# XM-15_Typical_Application_Circuit.net
KiCad netlist of a schematic drawn in Altium Designer
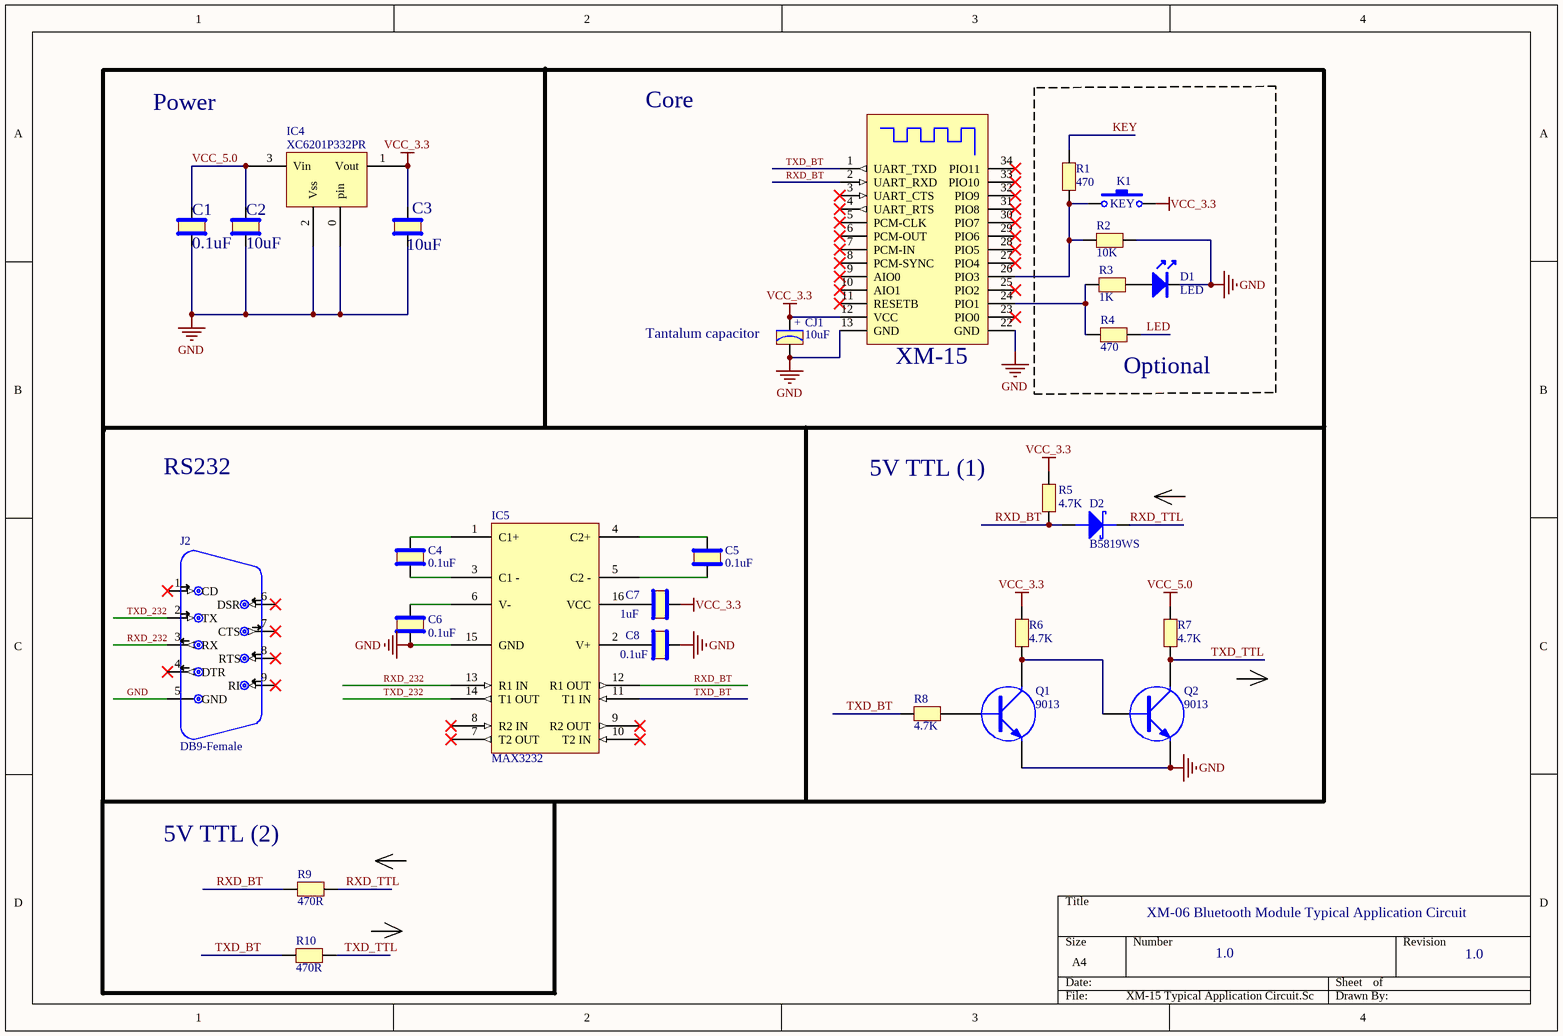
[diagram p0: XM-15 Typical Application Circuit.SchDoc]

(export (version "E")
  (design (tool "Eeschema 10.0.6"))
  (components
    (comp (ref "*1") (value "XM-15") (libsource (lib "wbh") (part "XM-101")))
    (comp (ref "C1") (value "0.1uF") (footprint "0603.RC") (libsource (lib "*") (part "CAP")))
    (comp (ref "C2") (value "10uF") (footprint "0603.RC") (libsource (lib "*") (part "CAP")))
    (comp (ref "C3") (value "10uF") (footprint "0603.RC") (libsource (lib "*") (part "CAP")))
    (comp (ref "C4") (value "0.1uF") (footprint "0603.RC") (libsource (lib "*") (part "CAP")))
    (comp (ref "C5") (value "0.1uF") (footprint "0603.RC") (libsource (lib "") (part "CAP_2")))
    (comp (ref "C6") (value "0.1uF") (footprint "0603.RC") (libsource (lib "*") (part "CAP")))
    (comp (ref "C7") (value "1uF") (footprint "0603.RC") (libsource (lib "") (part "CAP_1")))
    (comp (ref "C8") (value "0.1uF") (footprint "0603.RC") (libsource (lib "") (part "CAP_1")))
    (comp (ref "CJ1") (value "10uF") (footprint "1206.DC") (libsource (lib "wbh") (part "CAPJS")))
    (comp (ref "D1") (value "LED") (footprint "0603+") (libsource (lib "*") (part "LED")))
    (comp (ref "D2")
      (value "B5819WS")
      (footprint "SOD-323 - SMT")
      (description "Schottky Diode")
      (libsource (lib "wbh") (part "DIODE SCHOTTKY"))
    )
    (comp (ref "IC4") (value "XC6201P332PR") (footprint "SOT-89") (libsource (lib "*") (part "XC6201P301PR")))
    (comp (ref "IC5") (value "MAX3232") (footprint "SOP-16(N)") (libsource (lib "wbh") (part "MAX3232")))
    (comp (ref "J2") (value "DB9-Female") (footprint "DB9-F - 90") (libsource (lib "wbh") (part "DB9-F")))
    (comp (ref "K1") (value "KEY") (footprint "KEY-SS204") (libsource (lib "wbh") (part "SW-KEYSMT1")))
    (comp (ref "Q1")
      (value "9013")
      (footprint "SMT-SOT23MOS")
      (description "NPN Transistor")
      (libsource (lib "wbh") (part "NPN"))
    )
    (comp (ref "Q2")
      (value "9013")
      (footprint "SMT-SOT23MOS")
      (description "NPN Transistor")
      (libsource (lib "wbh") (part "NPN"))
    )
    (comp (ref "R1") (value "470") (footprint "0603.RC") (libsource (lib "") (part "RES_1")))
    (comp (ref "R2") (value "10K") (footprint "0603.RC") (libsource (lib "wbh") (part "RES")))
    (comp (ref "R3") (value "1K") (footprint "0603.RC") (libsource (lib "wbh") (part "RES")))
    (comp (ref "R4") (value "470") (footprint "0603.RC") (libsource (lib "wbh") (part "RES")))
    (comp (ref "R5") (value "4.7K") (footprint "0603.RC") (libsource (lib "") (part "RES_2")))
    (comp (ref "R6") (value "4.7K") (footprint "0603.RC") (libsource (lib "") (part "RES_3")))
    (comp (ref "R7") (value "4.7K") (footprint "0603.RC") (libsource (lib "") (part "RES_3")))
    (comp (ref "R8") (value "4.7K") (footprint "0603.RC") (libsource (lib "") (part "RES_1")))
    (comp (ref "R9") (value "470R") (footprint "0603.RC") (libsource (lib "") (part "RES_1")))
    (comp (ref "R10") (value "470R") (footprint "0603.RC") (libsource (lib "") (part "RES_1")))
  )
  (nets
    (net (code "1") (name "/KEY") (class "Default")
      (node (ref "R1") (pin "1") (pinfunction "1_1") (pintype "passive"))
    )
    (net (code "2") (name "/LED") (class "Default")
      (node (ref "R4") (pin "1") (pinfunction "1_1") (pintype "passive"))
    )
    (net (code "3") (name "/RXD_232") (class "Default")
      (node (ref "IC5") (pin "13") (pinfunction "R1_IN_13") (pintype "input"))
      (node (ref "J2") (pin "3") (pinfunction "RX_3") (pintype "output"))
    )
    (net (code "4") (name "/RXD_BT") (class "Default")
      (node (ref "*1") (pin "2") (pinfunction "UART_RXD_2") (pintype "input"))
      (node (ref "D2") (pin "1") (pinfunction "1_1") (pintype "passive"))
      (node (ref "IC5") (pin "12") (pinfunction "R1_OUT_12") (pintype "output"))
      (node (ref "R5") (pin "1") (pinfunction "1_1") (pintype "passive"))
      (node (ref "R9") (pin "2") (pinfunction "2_2") (pintype "passive"))
    )
    (net (code "5") (name "/RXD_TTL") (class "Default")
      (node (ref "D2") (pin "2") (pinfunction "2_2") (pintype "passive"))
      (node (ref "R9") (pin "1") (pinfunction "1_1") (pintype "passive"))
    )
    (net (code "6") (name "/TXD_232") (class "Default")
      (node (ref "IC5") (pin "14") (pinfunction "T1_OUT_14") (pintype "output"))
      (node (ref "J2") (pin "2") (pinfunction "TX_2") (pintype "input"))
    )
    (net (code "7") (name "/TXD_BT") (class "Default")
      (node (ref "*1") (pin "1") (pinfunction "UART_TXD_1") (pintype "output"))
      (node (ref "IC5") (pin "11") (pinfunction "T1_IN_11") (pintype "input"))
      (node (ref "R10") (pin "2") (pinfunction "2_2") (pintype "passive"))
      (node (ref "R8") (pin "2") (pinfunction "2_2") (pintype "passive"))
    )
    (net (code "8") (name "/TXD_TTL") (class "Default")
      (node (ref "Q2") (pin "D") (pinfunction "D_D") (pintype "passive"))
      (node (ref "R10") (pin "1") (pinfunction "1_1") (pintype "passive"))
      (node (ref "R7") (pin "1") (pinfunction "1_1") (pintype "passive"))
    )
    (net (code "9") (name "GND") (class "Default")
      (node (ref "*1") (pin "13") (pinfunction "GND_13") (pintype "passive"))
      (node (ref "*1") (pin "22") (pinfunction "GND_22") (pintype "passive"))
      (node (ref "C1") (pin "1") (pinfunction "1_1") (pintype "passive"))
      (node (ref "C2") (pin "1") (pinfunction "1_1") (pintype "passive"))
      (node (ref "C3") (pin "1") (pinfunction "1_1") (pintype "passive"))
      (node (ref "C6") (pin "1") (pinfunction "1_1") (pintype "passive"))
      (node (ref "C8") (pin "1") (pinfunction "1_1") (pintype "passive"))
      (node (ref "CJ1") (pin "K") (pinfunction "K_K") (pintype "passive"))
      (node (ref "D1") (pin "K") (pintype "passive"))
      (node (ref "IC4") (pin "0") (pinfunction "pin_0") (pintype "passive"))
      (node (ref "IC4") (pin "2") (pinfunction "Vss_2") (pintype "passive"))
      (node (ref "IC5") (pin "15") (pinfunction "GND_15") (pintype "power_in"))
      (node (ref "J2") (pin "5") (pinfunction "GND_5") (pintype "power_in"))
      (node (ref "Q1") (pin "S") (pinfunction "S_S") (pintype "passive"))
      (node (ref "Q2") (pin "S") (pinfunction "S_S") (pintype "passive"))
      (node (ref "R2") (pin "1") (pinfunction "1_1") (pintype "passive"))
    )
    (net (code "10") (name "Net-(*1-PIO1)") (class "Default")
      (node (ref "*1") (pin "24") (pinfunction "PIO1_24") (pintype "passive"))
      (node (ref "R3") (pin "2") (pinfunction "2_2") (pintype "passive"))
      (node (ref "R4") (pin "2") (pinfunction "2_2") (pintype "passive"))
    )
    (net (code "11") (name "Net-(*1-PIO3)") (class "Default")
      (node (ref "*1") (pin "26") (pinfunction "PIO3_26") (pintype "passive"))
      (node (ref "K1") (pin "2") (pinfunction "2_2") (pintype "passive"))
      (node (ref "R1") (pin "2") (pinfunction "2_2") (pintype "passive"))
      (node (ref "R2") (pin "2") (pinfunction "2_2") (pintype "passive"))
    )
    (net (code "12") (name "Net-(D1-PadA)") (class "Default")
      (node (ref "D1") (pin "A") (pintype "passive"))
      (node (ref "R3") (pin "1") (pinfunction "1_1") (pintype "passive"))
    )
    (net (code "13") (name "Net-(IC5-C1+)") (class "Default")
      (node (ref "C4") (pin "2") (pinfunction "2_2") (pintype "passive"))
      (node (ref "IC5") (pin "1") (pinfunction "C1+_1") (pintype "passive"))
    )
    (net (code "14") (name "Net-(IC5-C1_-)") (class "Default")
      (node (ref "C4") (pin "1") (pinfunction "1_1") (pintype "passive"))
      (node (ref "IC5") (pin "3") (pinfunction "C1_-_3") (pintype "passive"))
    )
    (net (code "15") (name "Net-(IC5-C2+)") (class "Default")
      (node (ref "C5") (pin "1") (pinfunction "1_1") (pintype "passive"))
      (node (ref "IC5") (pin "4") (pinfunction "C2+_4") (pintype "passive"))
    )
    (net (code "16") (name "Net-(IC5-C2_-)") (class "Default")
      (node (ref "C5") (pin "2") (pinfunction "2_2") (pintype "passive"))
      (node (ref "IC5") (pin "5") (pinfunction "C2_-_5") (pintype "passive"))
    )
    (net (code "17") (name "Net-(IC5-V+)") (class "Default")
      (node (ref "C8") (pin "2") (pinfunction "2_2") (pintype "passive"))
      (node (ref "IC5") (pin "2") (pinfunction "V+_2") (pintype "passive"))
    )
    (net (code "18") (name "Net-(IC5-V-)") (class "Default")
      (node (ref "C6") (pin "2") (pinfunction "2_2") (pintype "passive"))
      (node (ref "IC5") (pin "6") (pinfunction "V-_6") (pintype "power_in"))
    )
    (net (code "19") (name "Net-(IC5-VCC)") (class "Default")
      (node (ref "C7") (pin "2") (pinfunction "2_2") (pintype "passive"))
      (node (ref "IC5") (pin "16") (pinfunction "VCC_16") (pintype "power_in"))
    )
    (net (code "20") (name "Net-(Q1-PadD)") (class "Default")
      (node (ref "Q1") (pin "D") (pinfunction "D_D") (pintype "passive"))
      (node (ref "Q2") (pin "G") (pinfunction "G_G") (pintype "passive"))
      (node (ref "R6") (pin "1") (pinfunction "1_1") (pintype "passive"))
    )
    (net (code "21") (name "Net-(Q1-PadG)") (class "Default")
      (node (ref "Q1") (pin "G") (pinfunction "G_G") (pintype "passive"))
      (node (ref "R8") (pin "1") (pinfunction "1_1") (pintype "passive"))
    )
    (net (code "22") (name "VCC_3.3") (class "Default")
      (node (ref "*1") (pin "12") (pinfunction "VCC_12") (pintype "power_in"))
      (node (ref "C3") (pin "2") (pinfunction "2_2") (pintype "passive"))
      (node (ref "C7") (pin "1") (pinfunction "1_1") (pintype "passive"))
      (node (ref "CJ1") (pin "A") (pinfunction "A_A") (pintype "passive"))
      (node (ref "IC4") (pin "1") (pinfunction "Vout_1") (pintype "passive"))
      (node (ref "K1") (pin "1") (pinfunction "1_1") (pintype "passive"))
      (node (ref "R5") (pin "2") (pinfunction "2_2") (pintype "passive"))
      (node (ref "R6") (pin "2") (pinfunction "2_2") (pintype "passive"))
    )
    (net (code "23") (name "VCC_5.0") (class "Default")
      (node (ref "C1") (pin "2") (pinfunction "2_2") (pintype "passive"))
      (node (ref "C2") (pin "2") (pinfunction "2_2") (pintype "passive"))
      (node (ref "IC4") (pin "3") (pinfunction "Vin_3") (pintype "passive"))
      (node (ref "R7") (pin "2") (pinfunction "2_2") (pintype "passive"))
    )
    (net (code "24") (name "unconnected-(*1-AIO0-Pad9)") (class "Default")
      (node (ref "*1") (pin "9") (pinfunction "AIO0_9") (pintype "passive+no_connect"))
    )
    (net (code "25") (name "unconnected-(*1-AIO1-Pad10)") (class "Default")
      (node (ref "*1") (pin "10") (pinfunction "AIO1_10") (pintype "passive+no_connect"))
    )
    (net (code "26") (name "unconnected-(*1-PCM-CLK-Pad5)") (class "Default")
      (node (ref "*1") (pin "5") (pinfunction "PCM-CLK_5") (pintype "passive+no_connect"))
    )
    (net (code "27") (name "unconnected-(*1-PCM-IN-Pad7)") (class "Default")
      (node (ref "*1") (pin "7") (pinfunction "PCM-IN_7") (pintype "passive+no_connect"))
    )
    (net (code "28") (name "unconnected-(*1-PCM-OUT-Pad6)") (class "Default")
      (node (ref "*1") (pin "6") (pinfunction "PCM-OUT_6") (pintype "passive+no_connect"))
    )
    (net (code "29") (name "unconnected-(*1-PCM-SYNC-Pad8)") (class "Default")
      (node (ref "*1") (pin "8") (pinfunction "PCM-SYNC_8") (pintype "passive+no_connect"))
    )
    (net (code "30") (name "unconnected-(*1-PIO0-Pad23)") (class "Default")
      (node (ref "*1") (pin "23") (pinfunction "PIO0_23") (pintype "passive+no_connect"))
    )
    (net (code "31") (name "unconnected-(*1-PIO2-Pad25)") (class "Default")
      (node (ref "*1") (pin "25") (pinfunction "PIO2_25") (pintype "passive+no_connect"))
    )
    (net (code "32") (name "unconnected-(*1-PIO4-Pad27)") (class "Default")
      (node (ref "*1") (pin "27") (pinfunction "PIO4_27") (pintype "passive+no_connect"))
    )
    (net (code "33") (name "unconnected-(*1-PIO5-Pad28)") (class "Default")
      (node (ref "*1") (pin "28") (pinfunction "PIO5_28") (pintype "passive+no_connect"))
    )
    (net (code "34") (name "unconnected-(*1-PIO6-Pad29)") (class "Default")
      (node (ref "*1") (pin "29") (pinfunction "PIO6_29") (pintype "passive+no_connect"))
    )
    (net (code "35") (name "unconnected-(*1-PIO7-Pad30)") (class "Default")
      (node (ref "*1") (pin "30") (pinfunction "PIO7_30") (pintype "passive+no_connect"))
    )
    (net (code "36") (name "unconnected-(*1-PIO8-Pad31)") (class "Default")
      (node (ref "*1") (pin "31") (pinfunction "PIO8_31") (pintype "passive+no_connect"))
    )
    (net (code "37") (name "unconnected-(*1-PIO9-Pad32)") (class "Default")
      (node (ref "*1") (pin "32") (pinfunction "PIO9_32") (pintype "passive+no_connect"))
    )
    (net (code "38") (name "unconnected-(*1-PIO10-Pad33)") (class "Default")
      (node (ref "*1") (pin "33") (pinfunction "PIO10_33") (pintype "passive+no_connect"))
    )
    (net (code "39") (name "unconnected-(*1-PIO11-Pad34)") (class "Default")
      (node (ref "*1") (pin "34") (pinfunction "PIO11_34") (pintype "passive+no_connect"))
    )
    (net (code "40") (name "unconnected-(*1-RESETB-Pad11)") (class "Default")
      (node (ref "*1") (pin "11") (pinfunction "RESETB_11") (pintype "passive+no_connect"))
    )
    (net (code "41") (name "unconnected-(*1-UART_CTS-Pad3)") (class "Default")
      (node (ref "*1") (pin "3") (pinfunction "UART_CTS_3") (pintype "input+no_connect"))
    )
    (net (code "42") (name "unconnected-(*1-UART_RTS-Pad4)") (class "Default")
      (node (ref "*1") (pin "4") (pinfunction "UART_RTS_4") (pintype "output+no_connect"))
    )
    (net (code "43") (name "unconnected-(IC5-R2_IN-Pad8)") (class "Default")
      (node (ref "IC5") (pin "8") (pinfunction "R2_IN_8") (pintype "input+no_connect"))
    )
    (net (code "44") (name "unconnected-(IC5-R2_OUT-Pad9)") (class "Default")
      (node (ref "IC5") (pin "9") (pinfunction "R2_OUT_9") (pintype "output+no_connect"))
    )
    (net (code "45") (name "unconnected-(IC5-T2_IN-Pad10)") (class "Default")
      (node (ref "IC5") (pin "10") (pinfunction "T2_IN_10") (pintype "input+no_connect"))
    )
    (net (code "46") (name "unconnected-(IC5-T2_OUT-Pad7)") (class "Default")
      (node (ref "IC5") (pin "7") (pinfunction "T2_OUT_7") (pintype "output+no_connect"))
    )
    (net (code "47") (name "unconnected-(J2-CD-Pad1)") (class "Default")
      (node (ref "J2") (pin "1") (pinfunction "CD_1") (pintype "input+no_connect"))
    )
    (net (code "48") (name "unconnected-(J2-CTS-Pad7)") (class "Default")
      (node (ref "J2") (pin "7") (pinfunction "CTS_7") (pintype "output+no_connect"))
    )
    (net (code "49") (name "unconnected-(J2-DSR-Pad6)") (class "Default")
      (node (ref "J2") (pin "6") (pinfunction "DSR_6") (pintype "input+no_connect"))
    )
    (net (code "50") (name "unconnected-(J2-DTR-Pad4)") (class "Default")
      (node (ref "J2") (pin "4") (pinfunction "DTR_4") (pintype "output+no_connect"))
    )
    (net (code "51") (name "unconnected-(J2-RI-Pad9)") (class "Default")
      (node (ref "J2") (pin "9") (pinfunction "RI_9") (pintype "input+no_connect"))
    )
    (net (code "52") (name "unconnected-(J2-RTS-Pad8)") (class "Default")
      (node (ref "J2") (pin "8") (pinfunction "RTS_8") (pintype "input+no_connect"))
    )
  )
)
